# power_electronicsV2_1.net
KiCad netlist of a schematic drawn in EAGLE
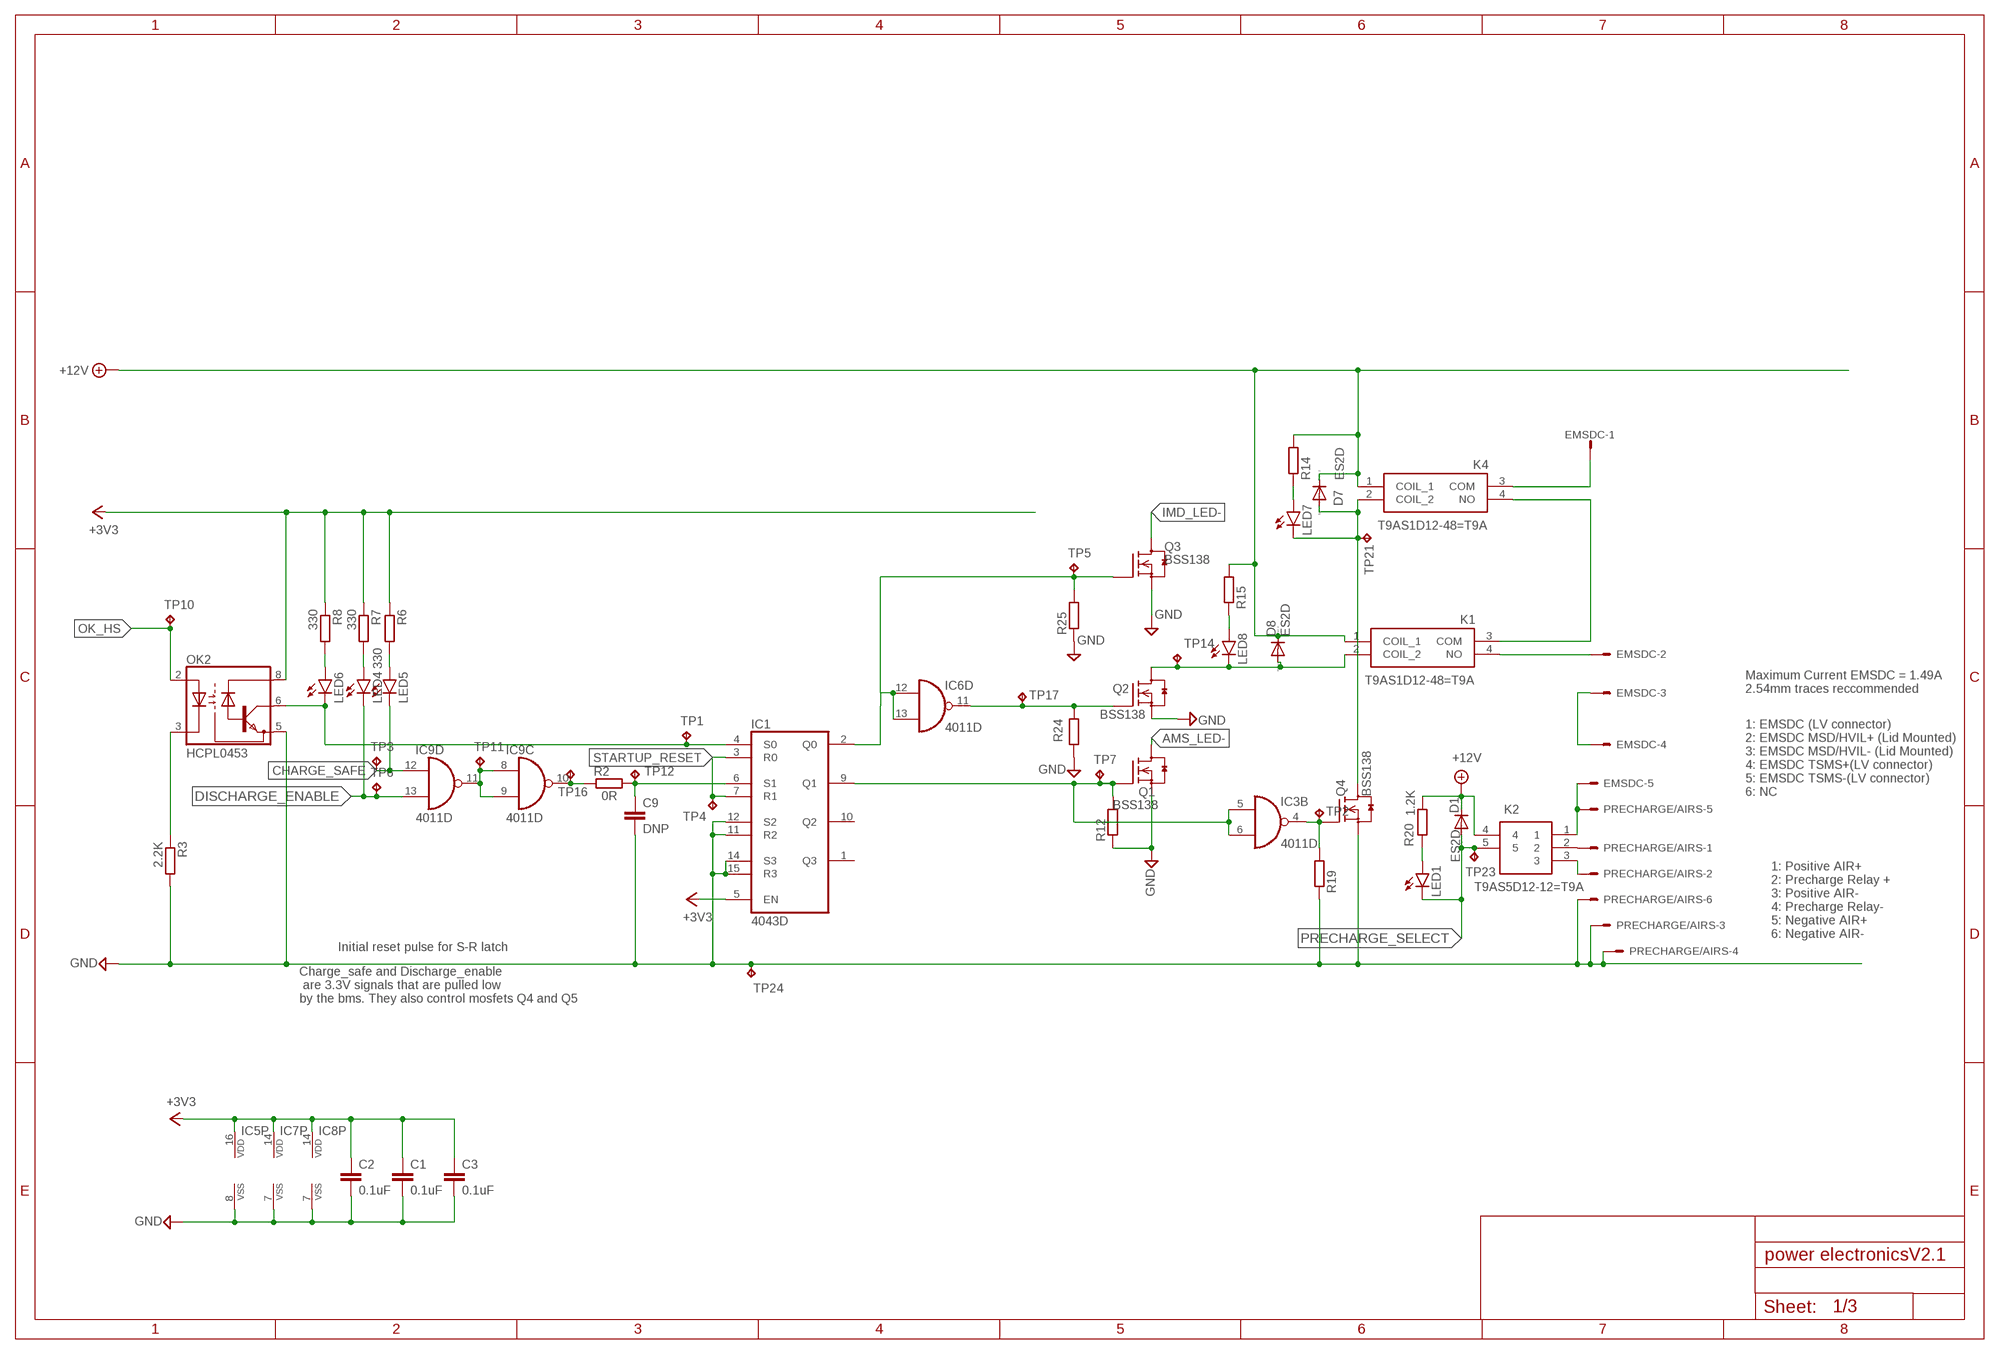
[diagram p0: schematic, sheet 1]
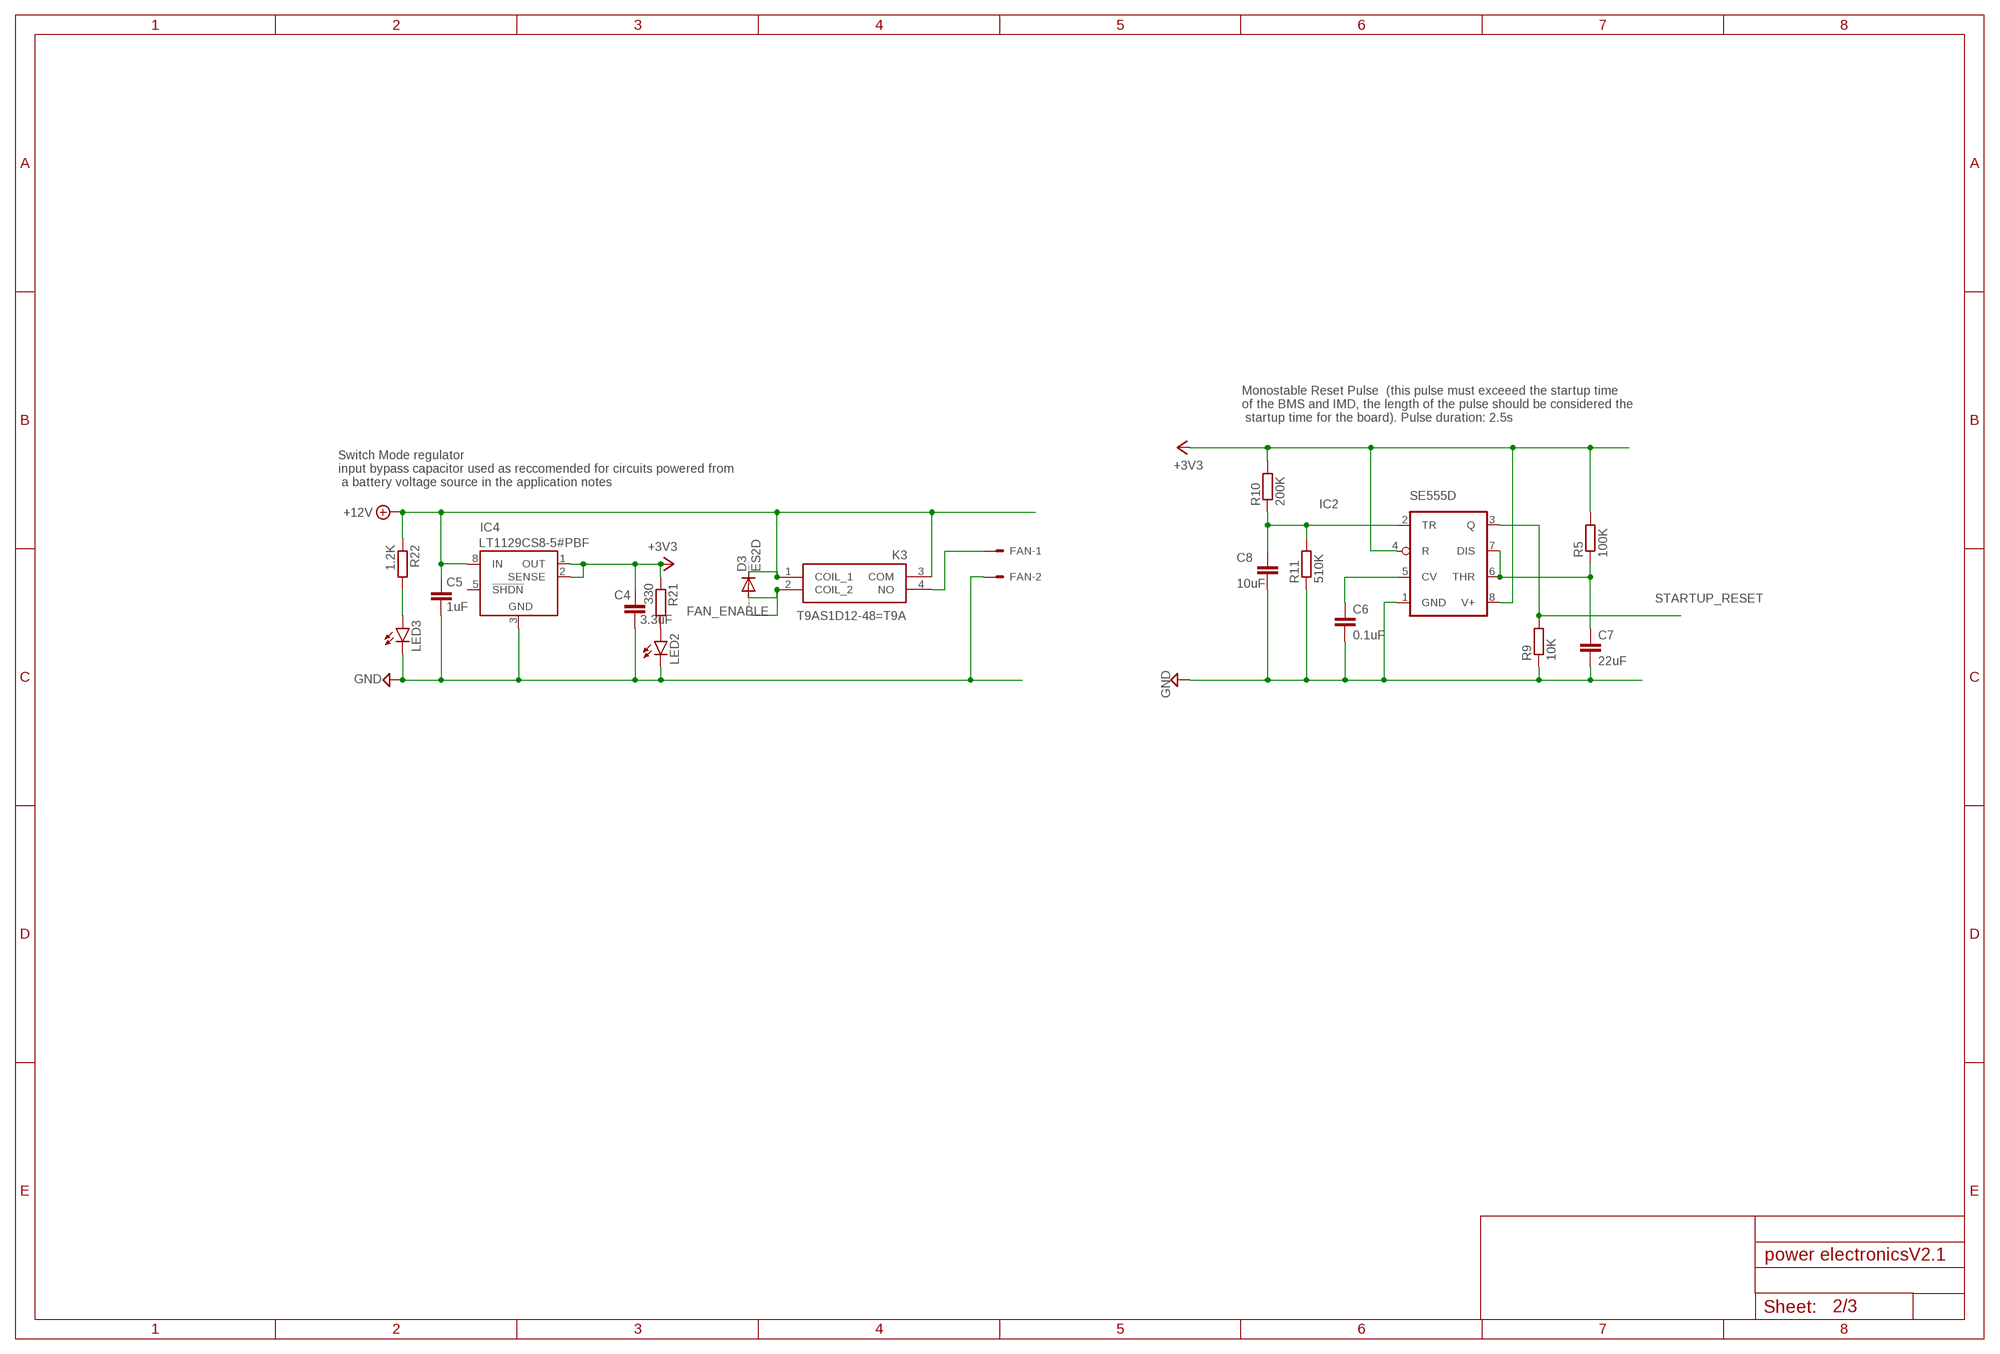
[diagram p1: schematic, sheet 2]
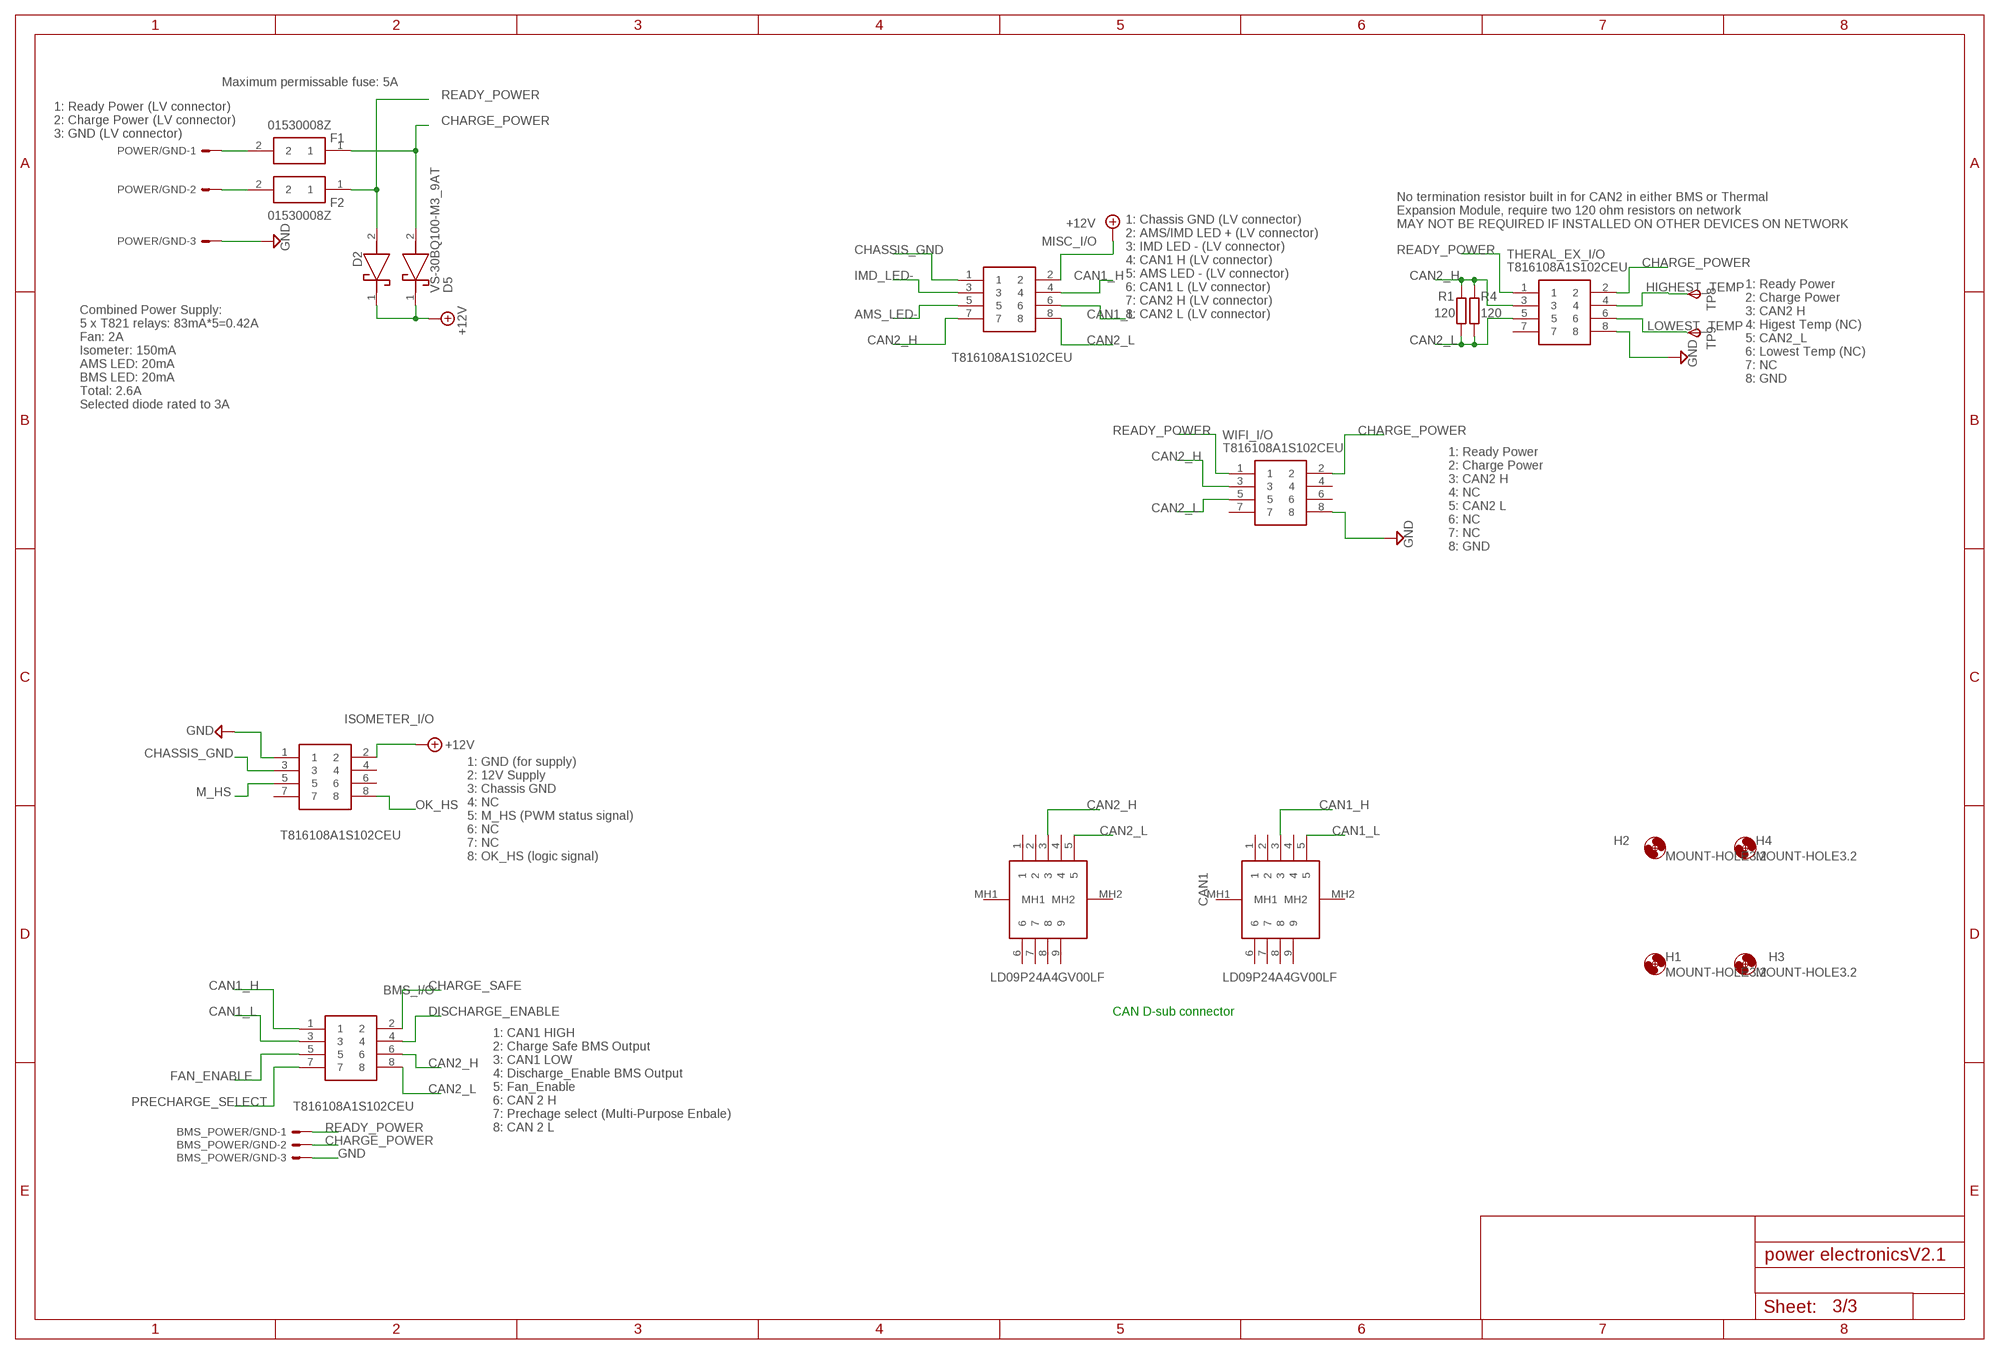
[diagram p2: schematic, sheet 3]

(export (version "E")
  (design (tool "Eeschema 10.0.6"))
  (components
    (comp (ref "BMS_I/O")
      (value "T816108A1S102CEU")
      (footprint "eagle-import:T816108A1S102CEU")
      (libsource (lib "eagle-import") (part "T816108A1S102CEU"))
    )
    (comp (ref "BMS_POWER/GND")
      (value "KK-156-3")
      (footprint "eagle-import:KK-156-3")
      (fields (field (name "MF") "MOLEX"))
      (libsource (lib "eagle-import") (part "KK-156-3"))
    )
    (comp (ref "CAN1")
      (value "LD09P24A4GV00LF")
      (footprint "eagle-import:LD09P24A4GV00LF")
      (fields (field (name "MOUSER_PART_NUMBER") "649-LD09P24A4GV00LF"))
      (libsource (lib "eagle-import") (part "LD09P24A4GV00LF"))
    )
    (comp (ref "CAN2")
      (value "LD09P24A4GV00LF")
      (footprint "eagle-import:LD09P24A4GV00LF")
      (fields (field (name "MOUSER_PART_NUMBER") "649-LD09P24A4GV00LF"))
      (libsource (lib "eagle-import") (part "LD09P24A4GV00LF"))
    )
    (comp (ref "D2")
      (value "VS-30BQ100-M3_9AT")
      (footprint "eagle-import:DIOM7959X262N")
      (fields
        (field (name "MANUFACTURER_PART_NUMBER") "VS-30BQ100-M3/9AT")
        (field (name "MOUSER_PART_NUMBER") "78-VS-30BQ100-M39AT")
      )
      (libsource (lib "eagle-import") (part "VS-30BQ100-M3_9AT"))
    )
    (comp (ref "D5")
      (value "VS-30BQ100-M3_9AT")
      (footprint "eagle-import:DIOM7959X262N")
      (fields
        (field (name "MANUFACTURER_PART_NUMBER") "VS-30BQ100-M3/9AT")
        (field (name "MOUSER_PART_NUMBER") "78-VS-30BQ100-M39AT")
      )
      (libsource (lib "eagle-import") (part "VS-30BQ100-M3_9AT"))
    )
    (comp (ref "F1")
      (value "01530008Z")
      (footprint "eagle-import:01530008")
      (fields (field (name "RS_PART_NUMBER") "3607317"))
      (libsource (lib "eagle-import") (part "01530008Z"))
    )
    (comp (ref "F2")
      (value "01530008Z")
      (footprint "eagle-import:01530008")
      (fields (field (name "RS_PART_NUMBER") "3607317"))
      (libsource (lib "eagle-import") (part "01530008Z"))
    )
    (comp (ref "H1")
      (value "MOUNT-HOLE3.2")
      (footprint "eagle-import:3,2")
      (libsource (lib "eagle-import") (part "MOUNT-HOLE3.2"))
    )
    (comp (ref "H2")
      (value "MOUNT-HOLE3.2")
      (footprint "eagle-import:3,2")
      (libsource (lib "eagle-import") (part "MOUNT-HOLE3.2"))
    )
    (comp (ref "H3")
      (value "MOUNT-HOLE3.2")
      (footprint "eagle-import:3,2")
      (libsource (lib "eagle-import") (part "MOUNT-HOLE3.2"))
    )
    (comp (ref "H4")
      (value "MOUNT-HOLE3.2")
      (footprint "eagle-import:3,2")
      (libsource (lib "eagle-import") (part "MOUNT-HOLE3.2"))
    )
    (comp (ref "ISOMETER_I/O")
      (value "T816108A1S102CEU")
      (footprint "eagle-import:T816108A1S102CEU")
      (libsource (lib "eagle-import") (part "T816108A1S102CEU"))
    )
    (comp (ref "MISC_I/O")
      (value "T816108A1S102CEU")
      (footprint "eagle-import:T816108A1S102CEU")
      (libsource (lib "eagle-import") (part "T816108A1S102CEU"))
    )
    (comp (ref "POWER/GND")
      (value "KK-156-3")
      (footprint "eagle-import:KK-156-3")
      (fields (field (name "MF") "MOLEX"))
      (libsource (lib "eagle-import") (part "KK-156-3"))
    )
    (comp (ref "R1")
      (value "120")
      (footprint "eagle-import:R1206")
      (libsource (lib "eagle-import") (part "R-EU_R1206"))
    )
    (comp (ref "R4")
      (value "120")
      (footprint "eagle-import:R1206")
      (libsource (lib "eagle-import") (part "R-EU_R1206"))
    )
    (comp (ref "THERAL_EX_I/O")
      (value "T816108A1S102CEU")
      (footprint "eagle-import:T816108A1S102CEU")
      (libsource (lib "eagle-import") (part "T816108A1S102CEU"))
    )
    (comp (ref "TP8")
      (value "TPSTP11R")
      (footprint "eagle-import:TP11R")
      (libsource (lib "eagle-import") (part "TPSTP11R"))
    )
    (comp (ref "TP9")
      (value "TPSTP11R")
      (footprint "eagle-import:TP11R")
      (libsource (lib "eagle-import") (part "TPSTP11R"))
    )
    (comp (ref "WIFI_I/O")
      (value "T816108A1S102CEU")
      (footprint "eagle-import:T816108A1S102CEU")
      (libsource (lib "eagle-import") (part "T816108A1S102CEU"))
    )
    (comp (ref "C1")
      (value "0.1uF")
      (footprint "eagle-import:C0805")
      (libsource (lib "eagle-import") (part "C-EUC0805"))
    )
    (comp (ref "C2")
      (value "0.1uF")
      (footprint "eagle-import:C0805")
      (libsource (lib "eagle-import") (part "C-EUC0805"))
    )
    (comp (ref "C3")
      (value "0.1uF")
      (footprint "eagle-import:C0805")
      (libsource (lib "eagle-import") (part "C-EUC0805"))
    )
    (comp (ref "C9")
      (value "DNP")
      (footprint "eagle-import:C0805K")
      (libsource (lib "eagle-import") (part "C-EUC0805K"))
    )
    (comp (ref "D1")
      (value "ES2D")
      (footprint "eagle-import:SMB")
      (libsource (lib "eagle-import") (part "ES2D"))
    )
    (comp (ref "D7")
      (value "ES2D")
      (footprint "eagle-import:SMB")
      (libsource (lib "eagle-import") (part "ES2D"))
    )
    (comp (ref "D8")
      (value "ES2D")
      (footprint "eagle-import:SMB")
      (libsource (lib "eagle-import") (part "ES2D"))
    )
    (comp (ref "EMSDC")
      (value "KK-156-6")
      (footprint "eagle-import:KK-156-6")
      (fields (field (name "MF") "MOLEX"))
      (libsource (lib "eagle-import") (part "KK-156-6"))
    )
    (comp (ref "IC1")
      (value "4043D")
      (footprint "eagle-import:SO16")
      (libsource (lib "eagle-import") (part "4043D"))
    )
    (comp (ref "IC3")
      (value "4011D")
      (footprint "eagle-import:SO14")
      (libsource (lib "eagle-import") (part "4011D"))
    )
    (comp (ref "IC5")
      (value "4043D")
      (footprint "eagle-import:SO16")
      (libsource (lib "eagle-import") (part "4043D"))
    )
    (comp (ref "IC6")
      (value "4011D")
      (footprint "eagle-import:SO14")
      (libsource (lib "eagle-import") (part "4011D"))
    )
    (comp (ref "IC7")
      (value "4011D")
      (footprint "eagle-import:SO14")
      (libsource (lib "eagle-import") (part "4011D"))
    )
    (comp (ref "IC8")
      (value "4011D")
      (footprint "eagle-import:SO14")
      (libsource (lib "eagle-import") (part "4011D"))
    )
    (comp (ref "IC9")
      (value "4011D")
      (footprint "eagle-import:SO14")
      (libsource (lib "eagle-import") (part "4011D"))
    )
    (comp (ref "K1")
      (value "T9AS1D12-48=T9A")
      (footprint "eagle-import:T9AS1D1248T9A")
      (fields (field (name "RS_PART_NUMBER") "6802534P"))
      (libsource (lib "eagle-import") (part "T9AS1D12-48=T9A"))
    )
    (comp (ref "K2")
      (value "T9AS5D12-12=T9A")
      (footprint "eagle-import:T9AS1D12")
      (fields (field (name "RS_PART_NUMBER") "6802528"))
      (libsource (lib "eagle-import") (part "T9AS5D12-12=T9A"))
    )
    (comp (ref "K4")
      (value "T9AS1D12-48=T9A")
      (footprint "eagle-import:T9AS1D1248T9A")
      (fields (field (name "RS_PART_NUMBER") "6802534P"))
      (libsource (lib "eagle-import") (part "T9AS1D12-48=T9A"))
    )
    (comp (ref "LED1")
      (value "LEDSML0805")
      (footprint "eagle-import:SML0805")
      (libsource (lib "eagle-import") (part "LEDSML0805"))
    )
    (comp (ref "LED4")
      (value "LEDSML0805")
      (footprint "eagle-import:SML0805")
      (libsource (lib "eagle-import") (part "LEDSML0805"))
    )
    (comp (ref "LED5")
      (value "LEDSML0805")
      (footprint "eagle-import:SML0805")
      (libsource (lib "eagle-import") (part "LEDSML0805"))
    )
    (comp (ref "LED6")
      (value "LEDSML0805")
      (footprint "eagle-import:SML0805")
      (libsource (lib "eagle-import") (part "LEDSML0805"))
    )
    (comp (ref "LED7")
      (value "LEDSML0805")
      (footprint "eagle-import:SML0805")
      (libsource (lib "eagle-import") (part "LEDSML0805"))
    )
    (comp (ref "LED8")
      (value "LEDSML0805")
      (footprint "eagle-import:SML0805")
      (libsource (lib "eagle-import") (part "LEDSML0805"))
    )
    (comp (ref "OK2")
      (value "HCPL0453")
      (footprint "eagle-import:SOIC08")
      (fields (field (name "MF") "AGILENT TECHNOLOGIES") (field (name "MPN") "HCPL-0453-000E"))
      (libsource (lib "eagle-import") (part "HCPL0453"))
    )
    (comp (ref "PRECHARGE/AIRS")
      (value "KK-156-6")
      (footprint "eagle-import:KK-156-6")
      (fields (field (name "MF") "MOLEX"))
      (libsource (lib "eagle-import") (part "KK-156-6"))
    )
    (comp (ref "Q1")
      (value "BSS138")
      (footprint "eagle-import:SOT23")
      (libsource (lib "eagle-import") (part "BSS138"))
    )
    (comp (ref "Q2")
      (value "BSS138")
      (footprint "eagle-import:SOT23")
      (libsource (lib "eagle-import") (part "BSS138"))
    )
    (comp (ref "Q3")
      (value "BSS138")
      (footprint "eagle-import:SOT23")
      (libsource (lib "eagle-import") (part "BSS138"))
    )
    (comp (ref "Q4")
      (value "BSS138")
      (footprint "eagle-import:SOT23")
      (libsource (lib "eagle-import") (part "BSS138"))
    )
    (comp (ref "R2")
      (value "0R")
      (footprint "eagle-import:R0805")
      (libsource (lib "eagle-import") (part "R-EU_R0805"))
    )
    (comp (ref "R3")
      (value "2.2K")
      (footprint "eagle-import:R0805")
      (libsource (lib "eagle-import") (part "R-EU_R0805"))
    )
    (comp (ref "R6")
      (value "330")
      (footprint "eagle-import:R0805")
      (libsource (lib "eagle-import") (part "R-EU_R0805"))
    )
    (comp (ref "R7")
      (value "330")
      (footprint "eagle-import:R0805")
      (libsource (lib "eagle-import") (part "R-EU_R0805"))
    )
    (comp (ref "R8")
      (value "330")
      (footprint "eagle-import:R0805")
      (libsource (lib "eagle-import") (part "R-EU_R0805"))
    )
    (comp (ref "R12")
      (value "R-EU_R0805")
      (footprint "eagle-import:R0805")
      (libsource (lib "eagle-import") (part "R-EU_R0805"))
    )
    (comp (ref "R14")
      (value "R-EU_R0805")
      (footprint "eagle-import:R0805")
      (libsource (lib "eagle-import") (part "R-EU_R0805"))
    )
    (comp (ref "R15")
      (value "R-EU_R0805")
      (footprint "eagle-import:R0805")
      (libsource (lib "eagle-import") (part "R-EU_R0805"))
    )
    (comp (ref "R19")
      (value "R-EU_R0805")
      (footprint "eagle-import:R0805")
      (libsource (lib "eagle-import") (part "R-EU_R0805"))
    )
    (comp (ref "R20")
      (value "1.2K")
      (footprint "eagle-import:R0805")
      (libsource (lib "eagle-import") (part "R-EU_R0805"))
    )
    (comp (ref "R24")
      (value "R-EU_R0805")
      (footprint "eagle-import:R0805")
      (libsource (lib "eagle-import") (part "R-EU_R0805"))
    )
    (comp (ref "R25")
      (value "R-EU_R0805")
      (footprint "eagle-import:R0805")
      (libsource (lib "eagle-import") (part "R-EU_R0805"))
    )
    (comp (ref "TP1")
      (value "TPPAD1-17")
      (footprint "eagle-import:P1-17")
      (libsource (lib "eagle-import") (part "TPPAD1-17"))
    )
    (comp (ref "TP2")
      (value "TPPAD1-17")
      (footprint "eagle-import:P1-17")
      (libsource (lib "eagle-import") (part "TPPAD1-17"))
    )
    (comp (ref "TP3")
      (value "TPPAD1-17")
      (footprint "eagle-import:P1-17")
      (libsource (lib "eagle-import") (part "TPPAD1-17"))
    )
    (comp (ref "TP4")
      (value "TPPAD1-17")
      (footprint "eagle-import:P1-17")
      (libsource (lib "eagle-import") (part "TPPAD1-17"))
    )
    (comp (ref "TP5")
      (value "TPPAD1-17")
      (footprint "eagle-import:P1-17")
      (libsource (lib "eagle-import") (part "TPPAD1-17"))
    )
    (comp (ref "TP6")
      (value "TPPAD1-17")
      (footprint "eagle-import:P1-17")
      (libsource (lib "eagle-import") (part "TPPAD1-17"))
    )
    (comp (ref "TP7")
      (value "TPPAD1-17")
      (footprint "eagle-import:P1-17")
      (libsource (lib "eagle-import") (part "TPPAD1-17"))
    )
    (comp (ref "TP10")
      (value "TPPAD1-17")
      (footprint "eagle-import:P1-17")
      (libsource (lib "eagle-import") (part "TPPAD1-17"))
    )
    (comp (ref "TP11")
      (value "TPPAD1-17")
      (footprint "eagle-import:P1-17")
      (libsource (lib "eagle-import") (part "TPPAD1-17"))
    )
    (comp (ref "TP12")
      (value "TPPAD1-17")
      (footprint "eagle-import:P1-17")
      (libsource (lib "eagle-import") (part "TPPAD1-17"))
    )
    (comp (ref "TP14")
      (value "TPPAD1-17")
      (footprint "eagle-import:P1-17")
      (libsource (lib "eagle-import") (part "TPPAD1-17"))
    )
    (comp (ref "TP16")
      (value "TPPAD1-17")
      (footprint "eagle-import:P1-17")
      (libsource (lib "eagle-import") (part "TPPAD1-17"))
    )
    (comp (ref "TP17")
      (value "TPPAD1-17")
      (footprint "eagle-import:P1-17")
      (libsource (lib "eagle-import") (part "TPPAD1-17"))
    )
    (comp (ref "TP21")
      (value "TPPAD1-17")
      (footprint "eagle-import:P1-17")
      (libsource (lib "eagle-import") (part "TPPAD1-17"))
    )
    (comp (ref "TP23")
      (value "TPPAD1-17")
      (footprint "eagle-import:P1-17")
      (libsource (lib "eagle-import") (part "TPPAD1-17"))
    )
    (comp (ref "TP24")
      (value "TPPAD1-17")
      (footprint "eagle-import:P1-17")
      (libsource (lib "eagle-import") (part "TPPAD1-17"))
    )
    (comp (ref "C4")
      (value "3.3uF")
      (footprint "eagle-import:C0805")
      (libsource (lib "eagle-import") (part "C-EUC0805"))
    )
    (comp (ref "C5")
      (value "1uF")
      (footprint "eagle-import:C0805")
      (libsource (lib "eagle-import") (part "C-EUC0805"))
    )
    (comp (ref "C6")
      (value "0.1uF")
      (footprint "eagle-import:C0805")
      (libsource (lib "eagle-import") (part "C-EUC0805"))
    )
    (comp (ref "C7")
      (value "22uF")
      (footprint "eagle-import:C1206")
      (libsource (lib "eagle-import") (part "C-EUC1206"))
    )
    (comp (ref "C8")
      (value "10uF")
      (footprint "eagle-import:C0805")
      (libsource (lib "eagle-import") (part "C-EUC0805"))
    )
    (comp (ref "D3")
      (value "ES2D")
      (footprint "eagle-import:SMB")
      (libsource (lib "eagle-import") (part "ES2D"))
    )
    (comp (ref "FAN")
      (value "KK-156-2")
      (footprint "eagle-import:KK-156-2")
      (fields (field (name "MF") "MOLEX"))
      (libsource (lib "eagle-import") (part "KK-156-2"))
    )
    (comp (ref "IC2")
      (value "SE555D")
      (footprint "eagle-import:SO08")
      (libsource (lib "eagle-import") (part "555DSE"))
    )
    (comp (ref "IC4")
      (value "LT1129CS8")
      (footprint "eagle-import:SOIC8")
      (fields (field (name "MPN") "LT1129CS8-5#PBF"))
      (libsource (lib "eagle-import") (part "LT1129CS8"))
    )
    (comp (ref "K3")
      (value "T9AS1D12-48=T9A")
      (footprint "eagle-import:T9AS1D1248T9A")
      (fields (field (name "RS_PART_NUMBER") "6802534P"))
      (libsource (lib "eagle-import") (part "T9AS1D12-48=T9A"))
    )
    (comp (ref "LED2")
      (value "LEDSML0805")
      (footprint "eagle-import:SML0805")
      (libsource (lib "eagle-import") (part "LEDSML0805"))
    )
    (comp (ref "LED3")
      (value "LEDSML0805")
      (footprint "eagle-import:SML0805")
      (libsource (lib "eagle-import") (part "LEDSML0805"))
    )
    (comp (ref "R5")
      (value "100K")
      (footprint "eagle-import:R0805")
      (libsource (lib "eagle-import") (part "R-EU_R0805"))
    )
    (comp (ref "R9")
      (value "10K")
      (footprint "eagle-import:R0805")
      (libsource (lib "eagle-import") (part "R-EU_R0805"))
    )
    (comp (ref "R10")
      (value "200K")
      (footprint "eagle-import:R0805")
      (libsource (lib "eagle-import") (part "R-EU_R0805"))
    )
    (comp (ref "R11")
      (value "510K")
      (footprint "eagle-import:R0805")
      (libsource (lib "eagle-import") (part "R-EU_R0805"))
    )
    (comp (ref "R21")
      (value "330")
      (footprint "eagle-import:R0805")
      (libsource (lib "eagle-import") (part "R-EU_R0805"))
    )
    (comp (ref "R22")
      (value "1.2K")
      (footprint "eagle-import:R0805")
      (libsource (lib "eagle-import") (part "R-EU_R0805"))
    )
  )
  (nets
    (net (code "1") (name "+3V3") (class "Default")
      (node (ref "C1") (pin "1") (pinfunction "1_1") (pintype "passive"))
      (node (ref "C2") (pin "1") (pinfunction "1_1") (pintype "passive"))
      (node (ref "C3") (pin "1") (pinfunction "1_1") (pintype "passive"))
      (node (ref "C4") (pin "1") (pinfunction "1_1") (pintype "passive"))
      (node (ref "IC1") (pin "5") (pinfunction "EN_5") (pintype "input"))
      (node (ref "IC2") (pin "4") (pinfunction "R_4") (pintype "input"))
      (node (ref "IC2") (pin "8") (pinfunction "V+_8") (pintype "power_in"))
      (node (ref "IC4") (pin "1") (pinfunction "OUT_1") (pintype "output"))
      (node (ref "IC4") (pin "2") (pinfunction "SENSE_2") (pintype "input"))
      (node (ref "IC5") (pin "16") (pinfunction "VDD_16") (pintype "power_in"))
      (node (ref "IC7") (pin "14") (pinfunction "VDD_14") (pintype "power_in"))
      (node (ref "IC8") (pin "14") (pinfunction "VDD_14") (pintype "power_in"))
      (node (ref "OK2") (pin "8") (pinfunction "VCC_8") (pintype "passive"))
      (node (ref "R10") (pin "2") (pinfunction "2_2") (pintype "passive"))
      (node (ref "R21") (pin "1") (pinfunction "1_1") (pintype "passive"))
      (node (ref "R5") (pin "2") (pinfunction "2_2") (pintype "passive"))
      (node (ref "R6") (pin "1") (pinfunction "1_1") (pintype "passive"))
      (node (ref "R7") (pin "1") (pinfunction "1_1") (pintype "passive"))
      (node (ref "R8") (pin "1") (pinfunction "1_1") (pintype "passive"))
    )
    (net (code "2") (name "+12V") (class "Default")
      (node (ref "C5") (pin "1") (pinfunction "1_1") (pintype "passive"))
      (node (ref "D1") (pin "C") (pinfunction "C_C") (pintype "passive"))
      (node (ref "D2") (pin "1") (pinfunction "K_1") (pintype "bidirectional"))
      (node (ref "D3") (pin "C") (pinfunction "C_C") (pintype "passive"))
      (node (ref "D5") (pin "1") (pinfunction "K_1") (pintype "bidirectional"))
      (node (ref "D7") (pin "C") (pinfunction "C_C") (pintype "passive"))
      (node (ref "D8") (pin "C") (pinfunction "C_C") (pintype "passive"))
      (node (ref "IC4") (pin "8") (pinfunction "IN_8") (pintype "input"))
      (node (ref "ISOMETER_I/O") (pin "2") (pinfunction "2_2") (pintype "bidirectional"))
      (node (ref "K1") (pin "1") (pinfunction "COIL_1_1") (pintype "bidirectional"))
      (node (ref "K2") (pin "4") (pinfunction "4_4") (pintype "bidirectional"))
      (node (ref "K3") (pin "1") (pinfunction "COIL_1_1") (pintype "bidirectional"))
      (node (ref "K3") (pin "3") (pinfunction "COM_3") (pintype "bidirectional"))
      (node (ref "K4") (pin "1") (pinfunction "COIL_1_1") (pintype "bidirectional"))
      (node (ref "MISC_I/O") (pin "2") (pinfunction "2_2") (pintype "bidirectional"))
      (node (ref "R14") (pin "2") (pinfunction "2_2") (pintype "passive"))
      (node (ref "R15") (pin "2") (pinfunction "2_2") (pintype "passive"))
      (node (ref "R20") (pin "1") (pinfunction "1_1") (pintype "passive"))
      (node (ref "R22") (pin "1") (pinfunction "1_1") (pintype "passive"))
    )
    (net (code "3") (name "AMS_LED-") (class "Default")
      (node (ref "MISC_I/O") (pin "5") (pinfunction "5_5") (pintype "bidirectional"))
      (node (ref "Q1") (pin "3") (pinfunction "D_3") (pintype "passive"))
    )
    (net (code "4") (name "CAN1_H") (class "Default")
      (node (ref "BMS_I/O") (pin "1") (pinfunction "1_1") (pintype "bidirectional"))
      (node (ref "CAN1") (pin "3") (pinfunction "3_3") (pintype "bidirectional"))
      (node (ref "MISC_I/O") (pin "4") (pinfunction "4_4") (pintype "bidirectional"))
    )
    (net (code "5") (name "CAN1_L") (class "Default")
      (node (ref "BMS_I/O") (pin "3") (pinfunction "3_3") (pintype "bidirectional"))
      (node (ref "CAN1") (pin "5") (pinfunction "5_5") (pintype "bidirectional"))
      (node (ref "MISC_I/O") (pin "6") (pinfunction "6_6") (pintype "bidirectional"))
    )
    (net (code "6") (name "CAN2_H") (class "Default")
      (node (ref "BMS_I/O") (pin "6") (pinfunction "6_6") (pintype "bidirectional"))
      (node (ref "CAN2") (pin "3") (pinfunction "3_3") (pintype "bidirectional"))
      (node (ref "MISC_I/O") (pin "7") (pinfunction "7_7") (pintype "bidirectional"))
      (node (ref "R1") (pin "1") (pinfunction "1_1") (pintype "passive"))
      (node (ref "R4") (pin "1") (pinfunction "1_1") (pintype "passive"))
      (node (ref "THERAL_EX_I/O") (pin "3") (pinfunction "3_3") (pintype "bidirectional"))
      (node (ref "WIFI_I/O") (pin "3") (pinfunction "3_3") (pintype "bidirectional"))
    )
    (net (code "7") (name "CAN2_L") (class "Default")
      (node (ref "BMS_I/O") (pin "8") (pinfunction "8_8") (pintype "bidirectional"))
      (node (ref "CAN2") (pin "5") (pinfunction "5_5") (pintype "bidirectional"))
      (node (ref "MISC_I/O") (pin "8") (pinfunction "8_8") (pintype "bidirectional"))
      (node (ref "R1") (pin "2") (pinfunction "2_2") (pintype "passive"))
      (node (ref "R4") (pin "2") (pinfunction "2_2") (pintype "passive"))
      (node (ref "THERAL_EX_I/O") (pin "5") (pinfunction "5_5") (pintype "bidirectional"))
      (node (ref "WIFI_I/O") (pin "5") (pinfunction "5_5") (pintype "bidirectional"))
    )
    (net (code "8") (name "CHARGE_POWER") (class "Default")
      (node (ref "BMS_POWER/GND") (pin "2") (pinfunction "S_2") (pintype "passive"))
      (node (ref "D5") (pin "2") (pinfunction "A_2") (pintype "bidirectional"))
      (node (ref "F1") (pin "1") (pinfunction "1_1") (pintype "bidirectional"))
      (node (ref "THERAL_EX_I/O") (pin "2") (pinfunction "2_2") (pintype "bidirectional"))
      (node (ref "WIFI_I/O") (pin "2") (pinfunction "2_2") (pintype "bidirectional"))
    )
    (net (code "9") (name "CHARGE_SAFE") (class "Default")
      (node (ref "BMS_I/O") (pin "2") (pinfunction "2_2") (pintype "bidirectional"))
      (node (ref "IC9") (pin "12") (pinfunction "I0_12") (pintype "input"))
      (node (ref "LED5") (pin "C") (pinfunction "C_C") (pintype "passive"))
      (node (ref "TP3") (pin "TP") (pinfunction "TP_TP") (pintype "input"))
    )
    (net (code "10") (name "CHASSIS_GND") (class "Default")
      (node (ref "ISOMETER_I/O") (pin "3") (pinfunction "3_3") (pintype "bidirectional"))
      (node (ref "MISC_I/O") (pin "1") (pinfunction "1_1") (pintype "bidirectional"))
    )
    (net (code "11") (name "DISCHARGE_ENABLE") (class "Default")
      (node (ref "BMS_I/O") (pin "4") (pinfunction "4_4") (pintype "bidirectional"))
      (node (ref "IC1") (pin "9") (pinfunction "Q1_9") (pintype "output"))
      (node (ref "IC3") (pin "5") (pinfunction "I0_5") (pintype "input"))
      (node (ref "IC3") (pin "6") (pinfunction "I1_6") (pintype "input"))
      (node (ref "IC9") (pin "13") (pinfunction "I1_13") (pintype "input"))
      (node (ref "LED4") (pin "C") (pinfunction "C_C") (pintype "passive"))
      (node (ref "Q1") (pin "1") (pinfunction "G_1") (pintype "passive"))
      (node (ref "R12") (pin "2") (pinfunction "2_2") (pintype "passive"))
      (node (ref "TP6") (pin "TP") (pinfunction "TP_TP") (pintype "input"))
      (node (ref "TP7") (pin "TP") (pinfunction "TP_TP") (pintype "input"))
    )
    (net (code "12") (name "FAN_ENABLE") (class "Default")
      (node (ref "BMS_I/O") (pin "5") (pinfunction "5_5") (pintype "bidirectional"))
      (node (ref "D3") (pin "A") (pinfunction "A_A") (pintype "passive"))
      (node (ref "K3") (pin "2") (pinfunction "COIL_2_2") (pintype "bidirectional"))
    )
    (net (code "13") (name "GND") (class "Default")
      (node (ref "BMS_POWER/GND") (pin "3") (pinfunction "S_3") (pintype "passive"))
      (node (ref "C1") (pin "2") (pinfunction "2_2") (pintype "passive"))
      (node (ref "C2") (pin "2") (pinfunction "2_2") (pintype "passive"))
      (node (ref "C3") (pin "2") (pinfunction "2_2") (pintype "passive"))
      (node (ref "C4") (pin "2") (pinfunction "2_2") (pintype "passive"))
      (node (ref "C5") (pin "2") (pinfunction "2_2") (pintype "passive"))
      (node (ref "C6") (pin "2") (pinfunction "2_2") (pintype "passive"))
      (node (ref "C7") (pin "2") (pinfunction "2_2") (pintype "passive"))
      (node (ref "C8") (pin "2") (pinfunction "2_2") (pintype "passive"))
      (node (ref "C9") (pin "2") (pinfunction "2_2") (pintype "passive"))
      (node (ref "FAN") (pin "2") (pinfunction "S_2") (pintype "passive"))
      (node (ref "IC1") (pin "11") (pinfunction "R2_11") (pintype "input"))
      (node (ref "IC1") (pin "12") (pinfunction "S2_12") (pintype "input"))
      (node (ref "IC1") (pin "14") (pinfunction "S3_14") (pintype "input"))
      (node (ref "IC1") (pin "15") (pinfunction "R3_15") (pintype "input"))
      (node (ref "IC2") (pin "1") (pinfunction "GND_1") (pintype "power_in"))
      (node (ref "IC4") (pin "3") (pinfunction "GND_3") (pintype "power_in"))
      (node (ref "IC5") (pin "8") (pinfunction "VSS_8") (pintype "power_in"))
      (node (ref "IC7") (pin "7") (pinfunction "VSS_7") (pintype "power_in"))
      (node (ref "IC8") (pin "7") (pinfunction "VSS_7") (pintype "power_in"))
      (node (ref "ISOMETER_I/O") (pin "1") (pinfunction "1_1") (pintype "bidirectional"))
      (node (ref "LED2") (pin "C") (pinfunction "C_C") (pintype "passive"))
      (node (ref "LED3") (pin "C") (pinfunction "C_C") (pintype "passive"))
      (node (ref "OK2") (pin "5") (pinfunction "GND_5") (pintype "passive"))
      (node (ref "POWER/GND") (pin "3") (pinfunction "S_3") (pintype "passive"))
      (node (ref "PRECHARGE/AIRS") (pin "3") (pinfunction "S_3") (pintype "passive"))
      (node (ref "PRECHARGE/AIRS") (pin "4") (pinfunction "S_4") (pintype "passive"))
      (node (ref "PRECHARGE/AIRS") (pin "6") (pinfunction "S_6") (pintype "passive"))
      (node (ref "Q1") (pin "2") (pinfunction "S_2") (pintype "passive"))
      (node (ref "Q2") (pin "2") (pinfunction "S_2") (pintype "passive"))
      (node (ref "Q3") (pin "2") (pinfunction "S_2") (pintype "passive"))
      (node (ref "Q4") (pin "2") (pinfunction "S_2") (pintype "passive"))
      (node (ref "R11") (pin "1") (pinfunction "1_1") (pintype "passive"))
      (node (ref "R12") (pin "1") (pinfunction "1_1") (pintype "passive"))
      (node (ref "R19") (pin "1") (pinfunction "1_1") (pintype "passive"))
      (node (ref "R24") (pin "1") (pinfunction "1_1") (pintype "passive"))
      (node (ref "R25") (pin "1") (pinfunction "1_1") (pintype "passive"))
      (node (ref "R3") (pin "2") (pinfunction "2_2") (pintype "passive"))
      (node (ref "R9") (pin "1") (pinfunction "1_1") (pintype "passive"))
      (node (ref "THERAL_EX_I/O") (pin "8") (pinfunction "8_8") (pintype "bidirectional"))
      (node (ref "TP24") (pin "TP") (pinfunction "TP_TP") (pintype "input"))
      (node (ref "WIFI_I/O") (pin "8") (pinfunction "8_8") (pintype "bidirectional"))
    )
    (net (code "14") (name "HIGHEST_TEMP") (class "Default")
      (node (ref "THERAL_EX_I/O") (pin "4") (pinfunction "4_4") (pintype "bidirectional"))
      (node (ref "TP8") (pin "TP") (pinfunction "PP_TP") (pintype "input"))
    )
    (net (code "15") (name "IMD_LED-") (class "Default")
      (node (ref "MISC_I/O") (pin "3") (pinfunction "3_3") (pintype "bidirectional"))
      (node (ref "Q3") (pin "3") (pinfunction "D_3") (pintype "passive"))
    )
    (net (code "16") (name "LOWEST_TEMP") (class "Default")
      (node (ref "THERAL_EX_I/O") (pin "6") (pinfunction "6_6") (pintype "bidirectional"))
      (node (ref "TP9") (pin "TP") (pinfunction "PP_TP") (pintype "input"))
    )
    (net (code "17") (name "M_HS") (class "Default")
      (node (ref "ISOMETER_I/O") (pin "5") (pinfunction "5_5") (pintype "bidirectional"))
    )
    (net (code "18") (name "Net-(EMSDCA-S)") (class "Default")
      (node (ref "EMSDC") (pin "1") (pinfunction "S_1") (pintype "passive"))
      (node (ref "K4") (pin "3") (pinfunction "COM_3") (pintype "bidirectional"))
    )
    (net (code "19") (name "Net-(EMSDCB-S)") (class "Default")
      (node (ref "EMSDC") (pin "2") (pinfunction "S_2") (pintype "passive"))
      (node (ref "K1") (pin "4") (pinfunction "NO_4") (pintype "bidirectional"))
    )
    (net (code "20") (name "Net-(EMSDCC-S)") (class "Default")
      (node (ref "EMSDC") (pin "3") (pinfunction "S_3") (pintype "passive"))
      (node (ref "EMSDC") (pin "4") (pinfunction "S_4") (pintype "passive"))
    )
    (net (code "21") (name "Net-(EMSDCE-S)") (class "Default")
      (node (ref "EMSDC") (pin "5") (pinfunction "S_5") (pintype "passive"))
      (node (ref "K2") (pin "1") (pinfunction "1_1") (pintype "bidirectional"))
      (node (ref "PRECHARGE/AIRS") (pin "5") (pinfunction "S_5") (pintype "passive"))
    )
    (net (code "22") (name "Net-(FANA-S)") (class "Default")
      (node (ref "FAN") (pin "1") (pinfunction "S_1") (pintype "passive"))
      (node (ref "K3") (pin "4") (pinfunction "NO_4") (pintype "bidirectional"))
    )
    (net (code "23") (name "Net-(IC1A-Q0)") (class "Default")
      (node (ref "IC1") (pin "2") (pinfunction "Q0_2") (pintype "output"))
      (node (ref "IC6") (pin "12") (pinfunction "I0_12") (pintype "input"))
      (node (ref "IC6") (pin "13") (pinfunction "I1_13") (pintype "input"))
      (node (ref "Q3") (pin "1") (pinfunction "G_1") (pintype "passive"))
      (node (ref "R25") (pin "2") (pinfunction "2_2") (pintype "passive"))
      (node (ref "TP5") (pin "TP") (pinfunction "TP_TP") (pintype "input"))
    )
    (net (code "24") (name "Net-(IC1A-S0)") (class "Default")
      (node (ref "IC1") (pin "4") (pinfunction "S0_4") (pintype "input"))
      (node (ref "LED6") (pin "C") (pinfunction "C_C") (pintype "passive"))
      (node (ref "OK2") (pin "6") (pinfunction "VO_6") (pintype "passive"))
      (node (ref "TP1") (pin "TP") (pinfunction "TP_TP") (pintype "input"))
    )
    (net (code "25") (name "Net-(IC1A-S1)") (class "Default")
      (node (ref "C9") (pin "1") (pinfunction "1_1") (pintype "passive"))
      (node (ref "IC1") (pin "6") (pinfunction "S1_6") (pintype "input"))
      (node (ref "R2") (pin "2") (pinfunction "2_2") (pintype "passive"))
      (node (ref "TP12") (pin "TP") (pinfunction "TP_TP") (pintype "input"))
    )
    (net (code "26") (name "Net-(IC2-CV)") (class "Default")
      (node (ref "C6") (pin "1") (pinfunction "1_1") (pintype "passive"))
      (node (ref "IC2") (pin "5") (pinfunction "CV_5") (pintype "input"))
    )
    (net (code "27") (name "Net-(IC2-DIS)") (class "Default")
      (node (ref "C7") (pin "1") (pinfunction "1_1") (pintype "passive"))
      (node (ref "IC2") (pin "6") (pinfunction "THR_6") (pintype "input"))
      (node (ref "IC2") (pin "7") (pinfunction "DIS_7") (pintype "input"))
      (node (ref "R5") (pin "1") (pinfunction "1_1") (pintype "passive"))
    )
    (net (code "28") (name "Net-(IC2-TR)") (class "Default")
      (node (ref "C8") (pin "1") (pinfunction "1_1") (pintype "passive"))
      (node (ref "IC2") (pin "2") (pinfunction "TR_2") (pintype "input"))
      (node (ref "R10") (pin "1") (pinfunction "1_1") (pintype "passive"))
      (node (ref "R11") (pin "2") (pinfunction "2_2") (pintype "passive"))
    )
    (net (code "29") (name "Net-(IC3B-O)") (class "Default")
      (node (ref "IC3") (pin "4") (pinfunction "O_4") (pintype "output"))
      (node (ref "Q4") (pin "1") (pinfunction "G_1") (pintype "passive"))
      (node (ref "R19") (pin "2") (pinfunction "2_2") (pintype "passive"))
      (node (ref "TP2") (pin "TP") (pinfunction "TP_TP") (pintype "input"))
    )
    (net (code "30") (name "Net-(IC6D-O)") (class "Default")
      (node (ref "IC6") (pin "11") (pinfunction "O_11") (pintype "output"))
      (node (ref "Q2") (pin "1") (pinfunction "G_1") (pintype "passive"))
      (node (ref "R24") (pin "2") (pinfunction "2_2") (pintype "passive"))
      (node (ref "TP17") (pin "TP") (pinfunction "TP_TP") (pintype "input"))
    )
    (net (code "31") (name "Net-(IC9C-I0)") (class "Default")
      (node (ref "IC9") (pin "11") (pinfunction "O_11") (pintype "output"))
      (node (ref "IC9") (pin "8") (pinfunction "I0_8") (pintype "input"))
      (node (ref "IC9") (pin "9") (pinfunction "I1_9") (pintype "input"))
      (node (ref "TP11") (pin "TP") (pinfunction "TP_TP") (pintype "input"))
    )
    (net (code "32") (name "Net-(IC9C-O)") (class "Default")
      (node (ref "IC9") (pin "10") (pinfunction "O_10") (pintype "output"))
      (node (ref "R2") (pin "1") (pinfunction "1_1") (pintype "passive"))
      (node (ref "TP16") (pin "TP") (pinfunction "TP_TP") (pintype "input"))
    )
    (net (code "33") (name "Net-(K1-COIL_2)") (class "Default")
      (node (ref "D8") (pin "A") (pinfunction "A_A") (pintype "passive"))
      (node (ref "K1") (pin "2") (pinfunction "COIL_2_2") (pintype "bidirectional"))
      (node (ref "LED8") (pin "C") (pinfunction "C_C") (pintype "passive"))
      (node (ref "Q2") (pin "3") (pinfunction "D_3") (pintype "passive"))
      (node (ref "TP14") (pin "TP") (pinfunction "TP_TP") (pintype "input"))
    )
    (net (code "34") (name "Net-(K1-COM)") (class "Default")
      (node (ref "K1") (pin "3") (pinfunction "COM_3") (pintype "bidirectional"))
      (node (ref "K4") (pin "4") (pinfunction "NO_4") (pintype "bidirectional"))
    )
    (net (code "35") (name "Net-(K4-COIL_2)") (class "Default")
      (node (ref "D7") (pin "A") (pinfunction "A_A") (pintype "passive"))
      (node (ref "K4") (pin "2") (pinfunction "COIL_2_2") (pintype "bidirectional"))
      (node (ref "LED7") (pin "C") (pinfunction "C_C") (pintype "passive"))
      (node (ref "Q4") (pin "3") (pinfunction "D_3") (pintype "passive"))
      (node (ref "TP21") (pin "TP") (pinfunction "TP_TP") (pintype "input"))
    )
    (net (code "36") (name "Net-(LED1-PadA)") (class "Default")
      (node (ref "LED1") (pin "A") (pinfunction "A_A") (pintype "passive"))
      (node (ref "R20") (pin "2") (pinfunction "2_2") (pintype "passive"))
    )
    (net (code "37") (name "Net-(LED2-PadA)") (class "Default")
      (node (ref "LED2") (pin "A") (pinfunction "A_A") (pintype "passive"))
      (node (ref "R21") (pin "2") (pinfunction "2_2") (pintype "passive"))
    )
    (net (code "38") (name "Net-(LED3-PadA)") (class "Default")
      (node (ref "LED3") (pin "A") (pinfunction "A_A") (pintype "passive"))
      (node (ref "R22") (pin "2") (pinfunction "2_2") (pintype "passive"))
    )
    (net (code "39") (name "Net-(LED4-PadA)") (class "Default")
      (node (ref "LED4") (pin "A") (pinfunction "A_A") (pintype "passive"))
      (node (ref "R7") (pin "2") (pinfunction "2_2") (pintype "passive"))
    )
    (net (code "40") (name "Net-(LED5-PadA)") (class "Default")
      (node (ref "LED5") (pin "A") (pinfunction "A_A") (pintype "passive"))
      (node (ref "R6") (pin "2") (pinfunction "2_2") (pintype "passive"))
    )
    (net (code "41") (name "Net-(LED6-PadA)") (class "Default")
      (node (ref "LED6") (pin "A") (pinfunction "A_A") (pintype "passive"))
      (node (ref "R8") (pin "2") (pinfunction "2_2") (pintype "passive"))
    )
    (net (code "42") (name "Net-(LED7-PadA)") (class "Default")
      (node (ref "LED7") (pin "A") (pinfunction "A_A") (pintype "passive"))
      (node (ref "R14") (pin "1") (pinfunction "1_1") (pintype "passive"))
    )
    (net (code "43") (name "Net-(LED8-PadA)") (class "Default")
      (node (ref "LED8") (pin "A") (pinfunction "A_A") (pintype "passive"))
      (node (ref "R15") (pin "1") (pinfunction "1_1") (pintype "passive"))
    )
    (net (code "44") (name "Net-(OK2-C)") (class "Default")
      (node (ref "OK2") (pin "3") (pinfunction "C_3") (pintype "passive"))
      (node (ref "R3") (pin "1") (pinfunction "1_1") (pintype "passive"))
    )
    (net (code "45") (name "Net-(POWER/GNDA-S)") (class "Default")
      (node (ref "F1") (pin "2") (pinfunction "2_2") (pintype "bidirectional"))
      (node (ref "POWER/GND") (pin "1") (pinfunction "S_1") (pintype "passive"))
    )
    (net (code "46") (name "Net-(POWER/GNDB-S)") (class "Default")
      (node (ref "F2") (pin "2") (pinfunction "2_2") (pintype "bidirectional"))
      (node (ref "POWER/GND") (pin "2") (pinfunction "S_2") (pintype "passive"))
    )
    (net (code "47") (name "Net-(PRECHARGE/AIRSA-S)") (class "Default")
      (node (ref "K2") (pin "2") (pinfunction "2_2") (pintype "bidirectional"))
      (node (ref "PRECHARGE/AIRS") (pin "1") (pinfunction "S_1") (pintype "passive"))
    )
    (net (code "48") (name "Net-(PRECHARGE/AIRSB-S)") (class "Default")
      (node (ref "K2") (pin "3") (pinfunction "3_3") (pintype "bidirectional"))
      (node (ref "PRECHARGE/AIRS") (pin "2") (pinfunction "S_2") (pintype "passive"))
    )
    (net (code "49") (name "OK_HS") (class "Default")
      (node (ref "ISOMETER_I/O") (pin "8") (pinfunction "8_8") (pintype "bidirectional"))
      (node (ref "OK2") (pin "2") (pinfunction "A_2") (pintype "passive"))
      (node (ref "TP10") (pin "TP") (pinfunction "TP_TP") (pintype "input"))
    )
    (net (code "50") (name "PRECHARGE_SELECT") (class "Default")
      (node (ref "BMS_I/O") (pin "7") (pinfunction "7_7") (pintype "bidirectional"))
      (node (ref "D1") (pin "A") (pinfunction "A_A") (pintype "passive"))
      (node (ref "K2") (pin "5") (pinfunction "5_5") (pintype "bidirectional"))
      (node (ref "LED1") (pin "C") (pinfunction "C_C") (pintype "passive"))
      (node (ref "TP23") (pin "TP") (pinfunction "TP_TP") (pintype "input"))
    )
    (net (code "51") (name "READY_POWER") (class "Default")
      (node (ref "BMS_POWER/GND") (pin "1") (pinfunction "S_1") (pintype "passive"))
      (node (ref "D2") (pin "2") (pinfunction "A_2") (pintype "bidirectional"))
      (node (ref "F2") (pin "1") (pinfunction "1_1") (pintype "bidirectional"))
      (node (ref "THERAL_EX_I/O") (pin "1") (pinfunction "1_1") (pintype "bidirectional"))
      (node (ref "WIFI_I/O") (pin "1") (pinfunction "1_1") (pintype "bidirectional"))
    )
    (net (code "52") (name "STARTUP_RESET") (class "Default")
      (node (ref "IC1") (pin "3") (pinfunction "R0_3") (pintype "input"))
      (node (ref "IC1") (pin "7") (pinfunction "R1_7") (pintype "input"))
      (node (ref "IC2") (pin "3") (pinfunction "Q_3") (pintype "output"))
      (node (ref "R9") (pin "2") (pinfunction "2_2") (pintype "passive"))
      (node (ref "TP4") (pin "TP") (pinfunction "TP_TP") (pintype "input"))
    )
    (net (code "53") (name "unconnected-(CAN1-Pad1)") (class "Default")
      (node (ref "CAN1") (pin "1") (pinfunction "1_1") (pintype "bidirectional"))
    )
    (net (code "54") (name "unconnected-(CAN1-Pad2)") (class "Default")
      (node (ref "CAN1") (pin "2") (pinfunction "2_2") (pintype "bidirectional"))
    )
    (net (code "55") (name "unconnected-(CAN1-Pad4)") (class "Default")
      (node (ref "CAN1") (pin "4") (pinfunction "4_4") (pintype "bidirectional"))
    )
    (net (code "56") (name "unconnected-(CAN1-Pad6)") (class "Default")
      (node (ref "CAN1") (pin "6") (pinfunction "6_6") (pintype "bidirectional"))
    )
    (net (code "57") (name "unconnected-(CAN1-Pad7)") (class "Default")
      (node (ref "CAN1") (pin "7") (pinfunction "7_7") (pintype "bidirectional"))
    )
    (net (code "58") (name "unconnected-(CAN1-Pad8)") (class "Default")
      (node (ref "CAN1") (pin "8") (pinfunction "8_8") (pintype "bidirectional"))
    )
    (net (code "59") (name "unconnected-(CAN1-Pad9)") (class "Default")
      (node (ref "CAN1") (pin "9") (pinfunction "9_9") (pintype "bidirectional"))
    )
    (net (code "60") (name "unconnected-(CAN1-PadMH1)") (class "Default")
      (node (ref "CAN1") (pin "MH1") (pinfunction "MH1_MH1") (pintype "bidirectional"))
    )
    (net (code "61") (name "unconnected-(CAN1-PadMH2)") (class "Default")
      (node (ref "CAN1") (pin "MH2") (pinfunction "MH2_MH2") (pintype "bidirectional"))
    )
    (net (code "62") (name "unconnected-(CAN2-Pad1)") (class "Default")
      (node (ref "CAN2") (pin "1") (pinfunction "1_1") (pintype "bidirectional"))
    )
    (net (code "63") (name "unconnected-(CAN2-Pad2)") (class "Default")
      (node (ref "CAN2") (pin "2") (pinfunction "2_2") (pintype "bidirectional"))
    )
    (net (code "64") (name "unconnected-(CAN2-Pad4)") (class "Default")
      (node (ref "CAN2") (pin "4") (pinfunction "4_4") (pintype "bidirectional"))
    )
    (net (code "65") (name "unconnected-(CAN2-Pad6)") (class "Default")
      (node (ref "CAN2") (pin "6") (pinfunction "6_6") (pintype "bidirectional"))
    )
    (net (code "66") (name "unconnected-(CAN2-Pad7)") (class "Default")
      (node (ref "CAN2") (pin "7") (pinfunction "7_7") (pintype "bidirectional"))
    )
    (net (code "67") (name "unconnected-(CAN2-Pad8)") (class "Default")
      (node (ref "CAN2") (pin "8") (pinfunction "8_8") (pintype "bidirectional"))
    )
    (net (code "68") (name "unconnected-(CAN2-Pad9)") (class "Default")
      (node (ref "CAN2") (pin "9") (pinfunction "9_9") (pintype "bidirectional"))
    )
    (net (code "69") (name "unconnected-(CAN2-PadMH1)") (class "Default")
      (node (ref "CAN2") (pin "MH1") (pinfunction "MH1_MH1") (pintype "bidirectional"))
    )
    (net (code "70") (name "unconnected-(CAN2-PadMH2)") (class "Default")
      (node (ref "CAN2") (pin "MH2") (pinfunction "MH2_MH2") (pintype "bidirectional"))
    )
    (net (code "71") (name "unconnected-(IC1A-Q2-Pad10)") (class "Default")
      (node (ref "IC1") (pin "10") (pinfunction "Q2_10") (pintype "output"))
    )
    (net (code "72") (name "unconnected-(IC1A-Q3-Pad1)") (class "Default")
      (node (ref "IC1") (pin "1") (pinfunction "Q3_1") (pintype "output"))
    )
    (net (code "73") (name "unconnected-(IC4A-~{SHDN}-Pad5)") (class "Default")
      (node (ref "IC4") (pin "5") (pinfunction "~{SHDN}_5") (pintype "input"))
    )
    (net (code "74") (name "unconnected-(ISOMETER_I/O-Pad4)") (class "Default")
      (node (ref "ISOMETER_I/O") (pin "4") (pinfunction "4_4") (pintype "bidirectional"))
    )
    (net (code "75") (name "unconnected-(ISOMETER_I/O-Pad6)") (class "Default")
      (node (ref "ISOMETER_I/O") (pin "6") (pinfunction "6_6") (pintype "bidirectional"))
    )
    (net (code "76") (name "unconnected-(ISOMETER_I/O-Pad7)") (class "Default")
      (node (ref "ISOMETER_I/O") (pin "7") (pinfunction "7_7") (pintype "bidirectional"))
    )
    (net (code "77") (name "unconnected-(THERAL_EX_I/O-Pad7)") (class "Default")
      (node (ref "THERAL_EX_I/O") (pin "7") (pinfunction "7_7") (pintype "bidirectional"))
    )
    (net (code "78") (name "unconnected-(WIFI_I/O-Pad4)") (class "Default")
      (node (ref "WIFI_I/O") (pin "4") (pinfunction "4_4") (pintype "bidirectional"))
    )
    (net (code "79") (name "unconnected-(WIFI_I/O-Pad6)") (class "Default")
      (node (ref "WIFI_I/O") (pin "6") (pinfunction "6_6") (pintype "bidirectional"))
    )
    (net (code "80") (name "unconnected-(WIFI_I/O-Pad7)") (class "Default")
      (node (ref "WIFI_I/O") (pin "7") (pinfunction "7_7") (pintype "bidirectional"))
    )
  )
)
